# esp8266-blynk.net
KiCad netlist of a schematic drawn in EAGLE
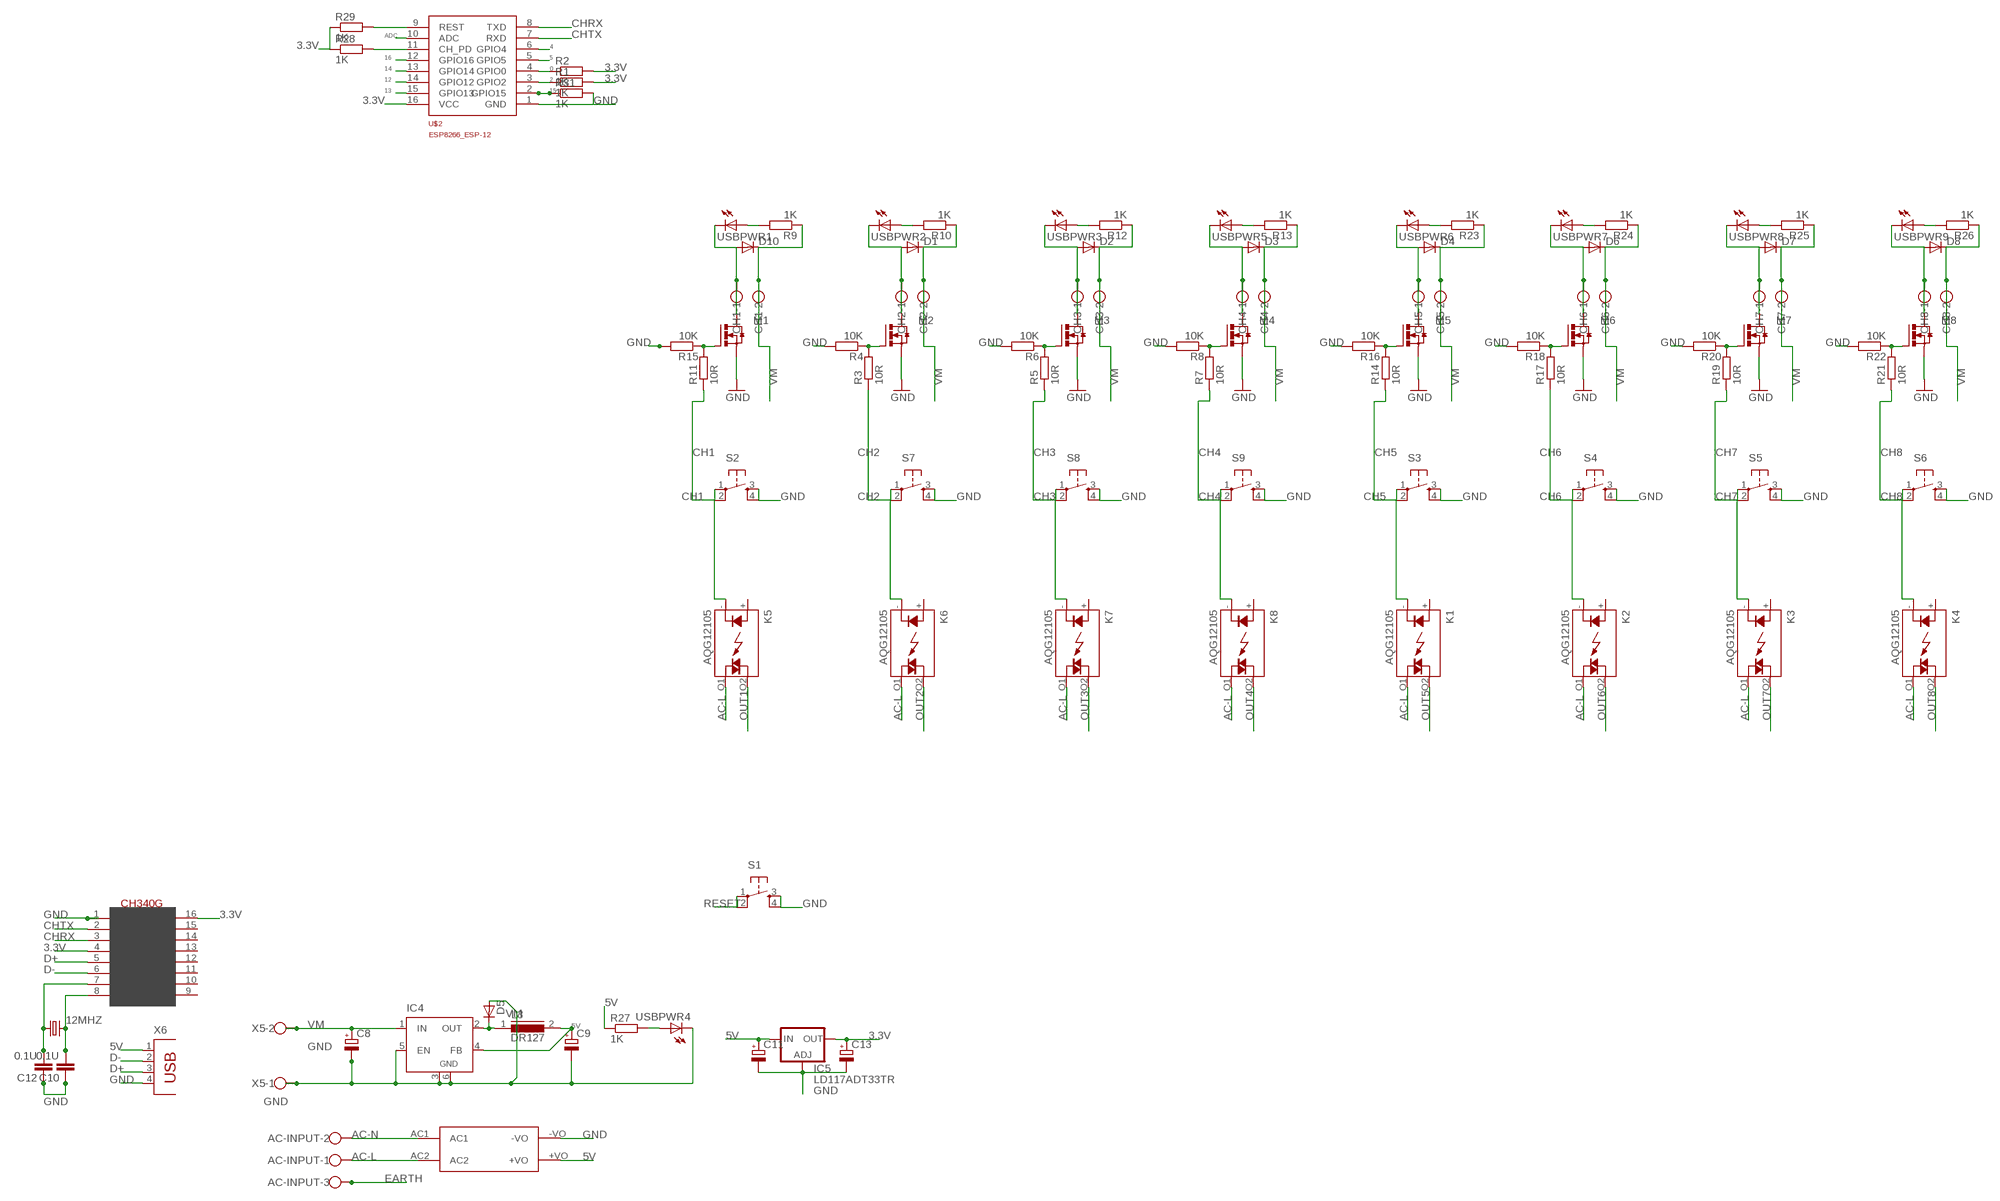
[diagram p0: schematic, sheet 1]

(export (version "E")
  (design (tool "Eeschema 10.0.6"))
  (components
    (comp (ref "12MHZ")
      (value "CRYSTALHC49UP")
      (footprint "eagle-import:HC49UP")
      (libsource (lib "eagle-import") (part "CRYSTALHC49UP"))
    )
    (comp (ref "AC-INPUT")
      (value "W237-103")
      (footprint "eagle-import:W237-103")
      (fields (field (name "MPN") "237-103"))
      (libsource (lib "eagle-import") (part "W237-103"))
    )
    (comp (ref "C8")
      (value "CPOL-EUE")
      (footprint "eagle-import:PANASONIC_E")
      (libsource (lib "eagle-import") (part "resistor_CPOL-EUE"))
    )
    (comp (ref "C9")
      (value "CPOL-EUE")
      (footprint "eagle-import:PANASONIC_E")
      (libsource (lib "eagle-import") (part "resistor_CPOL-EUE"))
    )
    (comp (ref "C10")
      (value "0.1U")
      (footprint "eagle-import:C1206")
      (libsource (lib "eagle-import") (part "C-EUC1206"))
    )
    (comp (ref "C11")
      (value "CPOL-EUC")
      (footprint "eagle-import:PANASONIC_C")
      (libsource (lib "eagle-import") (part "CPOL-EUC"))
    )
    (comp (ref "C12")
      (value "0.1U")
      (footprint "eagle-import:C1206")
      (libsource (lib "eagle-import") (part "C-EUC1206"))
    )
    (comp (ref "C13")
      (value "CPOL-EUC")
      (footprint "eagle-import:PANASONIC_C")
      (libsource (lib "eagle-import") (part "CPOL-EUC"))
    )
    (comp (ref "CH1")
      (value "W237-102")
      (footprint "eagle-import:W237-102")
      (fields (field (name "MPN") "237-102"))
      (libsource (lib "eagle-import") (part "W237-102"))
    )
    (comp (ref "CH2")
      (value "W237-102")
      (footprint "eagle-import:W237-102")
      (fields (field (name "MPN") "237-102"))
      (libsource (lib "eagle-import") (part "W237-102"))
    )
    (comp (ref "CH3")
      (value "W237-102")
      (footprint "eagle-import:W237-102")
      (fields (field (name "MPN") "237-102"))
      (libsource (lib "eagle-import") (part "W237-102"))
    )
    (comp (ref "CH4")
      (value "W237-102")
      (footprint "eagle-import:W237-102")
      (fields (field (name "MPN") "237-102"))
      (libsource (lib "eagle-import") (part "W237-102"))
    )
    (comp (ref "CH5")
      (value "W237-102")
      (footprint "eagle-import:W237-102")
      (fields (field (name "MPN") "237-102"))
      (libsource (lib "eagle-import") (part "W237-102"))
    )
    (comp (ref "CH6")
      (value "W237-102")
      (footprint "eagle-import:W237-102")
      (fields (field (name "MPN") "237-102"))
      (libsource (lib "eagle-import") (part "W237-102"))
    )
    (comp (ref "CH7")
      (value "W237-102")
      (footprint "eagle-import:W237-102")
      (fields (field (name "MPN") "237-102"))
      (libsource (lib "eagle-import") (part "W237-102"))
    )
    (comp (ref "CH8")
      (value "W237-102")
      (footprint "eagle-import:W237-102")
      (fields (field (name "MPN") "237-102"))
      (libsource (lib "eagle-import") (part "W237-102"))
    )
    (comp (ref "D1")
      (value "DIODESMA-ALT")
      (footprint "eagle-import:SMA-DIODE_ALT")
      (libsource (lib "eagle-import") (part "DIODESMA-ALT"))
    )
    (comp (ref "D2")
      (value "DIODESMA-ALT")
      (footprint "eagle-import:SMA-DIODE_ALT")
      (libsource (lib "eagle-import") (part "DIODESMA-ALT"))
    )
    (comp (ref "D3")
      (value "DIODESMA-ALT")
      (footprint "eagle-import:SMA-DIODE_ALT")
      (libsource (lib "eagle-import") (part "DIODESMA-ALT"))
    )
    (comp (ref "D4")
      (value "DIODESMA-ALT")
      (footprint "eagle-import:SMA-DIODE_ALT")
      (libsource (lib "eagle-import") (part "DIODESMA-ALT"))
    )
    (comp (ref "D5")
      (value "D-SOD-87")
      (footprint "eagle-import:SOD87")
      (libsource (lib "eagle-import") (part "D-SOD-87"))
    )
    (comp (ref "D6")
      (value "DIODESMA-ALT")
      (footprint "eagle-import:SMA-DIODE_ALT")
      (libsource (lib "eagle-import") (part "DIODESMA-ALT"))
    )
    (comp (ref "D7")
      (value "DIODESMA-ALT")
      (footprint "eagle-import:SMA-DIODE_ALT")
      (libsource (lib "eagle-import") (part "DIODESMA-ALT"))
    )
    (comp (ref "D8")
      (value "DIODESMA-ALT")
      (footprint "eagle-import:SMA-DIODE_ALT")
      (libsource (lib "eagle-import") (part "DIODESMA-ALT"))
    )
    (comp (ref "D10")
      (value "DIODESMA-ALT")
      (footprint "eagle-import:SMA-DIODE_ALT")
      (libsource (lib "eagle-import") (part "DIODESMA-ALT"))
    )
    (comp (ref "IC4")
      (value "LM2596S")
      (footprint "eagle-import:TO263-5")
      (libsource (lib "eagle-import") (part "LM2596S"))
    )
    (comp (ref "IC5")
      (value "LD117ADT33TR")
      (footprint "eagle-import:DPACK")
      (libsource (lib "eagle-import") (part "LD117A?DT33TR"))
    )
    (comp (ref "K1")
      (value "AQG12105")
      (footprint "eagle-import:AQG")
      (fields (field (name "MF") "AROMAT/ MATSUSHITA"))
      (libsource (lib "eagle-import") (part "AQG12105"))
    )
    (comp (ref "K2")
      (value "AQG12105")
      (footprint "eagle-import:AQG")
      (fields (field (name "MF") "AROMAT/ MATSUSHITA"))
      (libsource (lib "eagle-import") (part "AQG12105"))
    )
    (comp (ref "K3")
      (value "AQG12105")
      (footprint "eagle-import:AQG")
      (fields (field (name "MF") "AROMAT/ MATSUSHITA"))
      (libsource (lib "eagle-import") (part "AQG12105"))
    )
    (comp (ref "K4")
      (value "AQG12105")
      (footprint "eagle-import:AQG")
      (fields (field (name "MF") "AROMAT/ MATSUSHITA"))
      (libsource (lib "eagle-import") (part "AQG12105"))
    )
    (comp (ref "K5")
      (value "AQG12105")
      (footprint "eagle-import:AQG")
      (fields (field (name "MF") "AROMAT/ MATSUSHITA"))
      (libsource (lib "eagle-import") (part "AQG12105"))
    )
    (comp (ref "K6")
      (value "AQG12105")
      (footprint "eagle-import:AQG")
      (fields (field (name "MF") "AROMAT/ MATSUSHITA"))
      (libsource (lib "eagle-import") (part "AQG12105"))
    )
    (comp (ref "K7")
      (value "AQG12105")
      (footprint "eagle-import:AQG")
      (fields (field (name "MF") "AROMAT/ MATSUSHITA"))
      (libsource (lib "eagle-import") (part "AQG12105"))
    )
    (comp (ref "K8")
      (value "AQG12105")
      (footprint "eagle-import:AQG")
      (fields (field (name "MF") "AROMAT/ MATSUSHITA"))
      (libsource (lib "eagle-import") (part "AQG12105"))
    )
    (comp (ref "L3")
      (value "DR127")
      (footprint "eagle-import:DR127")
      (libsource (lib "eagle-import") (part "DR127"))
    )
    (comp (ref "M1")
      (value "IRLR024N")
      (footprint "eagle-import:TO252")
      (libsource (lib "eagle-import") (part "IRLR024N"))
    )
    (comp (ref "M2")
      (value "IRLR024N")
      (footprint "eagle-import:TO252")
      (libsource (lib "eagle-import") (part "IRLR024N"))
    )
    (comp (ref "M3")
      (value "IRLR024N")
      (footprint "eagle-import:TO252")
      (libsource (lib "eagle-import") (part "IRLR024N"))
    )
    (comp (ref "M4")
      (value "IRLR024N")
      (footprint "eagle-import:TO252")
      (libsource (lib "eagle-import") (part "IRLR024N"))
    )
    (comp (ref "M5")
      (value "IRLR024N")
      (footprint "eagle-import:TO252")
      (libsource (lib "eagle-import") (part "IRLR024N"))
    )
    (comp (ref "M6")
      (value "IRLR024N")
      (footprint "eagle-import:TO252")
      (libsource (lib "eagle-import") (part "IRLR024N"))
    )
    (comp (ref "M7")
      (value "IRLR024N")
      (footprint "eagle-import:TO252")
      (libsource (lib "eagle-import") (part "IRLR024N"))
    )
    (comp (ref "M8")
      (value "IRLR024N")
      (footprint "eagle-import:TO252")
      (libsource (lib "eagle-import") (part "IRLR024N"))
    )
    (comp (ref "R1")
      (value "1K")
      (footprint "eagle-import:M1206")
      (libsource (lib "eagle-import") (part "R-EU_M1206"))
    )
    (comp (ref "R2")
      (value "1K")
      (footprint "eagle-import:M1206")
      (libsource (lib "eagle-import") (part "R-EU_M1206"))
    )
    (comp (ref "R3")
      (value "10R")
      (footprint "eagle-import:M1206")
      (libsource (lib "eagle-import") (part "resistor_R-EU_M1206"))
    )
    (comp (ref "R4")
      (value "10K")
      (footprint "eagle-import:M1206")
      (libsource (lib "eagle-import") (part "resistor_R-EU_M1206"))
    )
    (comp (ref "R5")
      (value "10R")
      (footprint "eagle-import:M1206")
      (libsource (lib "eagle-import") (part "resistor_R-EU_M1206"))
    )
    (comp (ref "R6")
      (value "10K")
      (footprint "eagle-import:M1206")
      (libsource (lib "eagle-import") (part "resistor_R-EU_M1206"))
    )
    (comp (ref "R7")
      (value "10R")
      (footprint "eagle-import:M1206")
      (libsource (lib "eagle-import") (part "resistor_R-EU_M1206"))
    )
    (comp (ref "R8")
      (value "10K")
      (footprint "eagle-import:M1206")
      (libsource (lib "eagle-import") (part "resistor_R-EU_M1206"))
    )
    (comp (ref "R9")
      (value "1K")
      (footprint "eagle-import:M1206")
      (libsource (lib "eagle-import") (part "R-EU_M1206"))
    )
    (comp (ref "R10")
      (value "1K")
      (footprint "eagle-import:M1206")
      (libsource (lib "eagle-import") (part "R-EU_M1206"))
    )
    (comp (ref "R11")
      (value "10R")
      (footprint "eagle-import:M1206")
      (libsource (lib "eagle-import") (part "resistor_R-EU_M1206"))
    )
    (comp (ref "R12")
      (value "1K")
      (footprint "eagle-import:M1206")
      (libsource (lib "eagle-import") (part "R-EU_M1206"))
    )
    (comp (ref "R13")
      (value "1K")
      (footprint "eagle-import:M1206")
      (libsource (lib "eagle-import") (part "R-EU_M1206"))
    )
    (comp (ref "R14")
      (value "10R")
      (footprint "eagle-import:M1206")
      (libsource (lib "eagle-import") (part "resistor_R-EU_M1206"))
    )
    (comp (ref "R15")
      (value "10K")
      (footprint "eagle-import:M1206")
      (libsource (lib "eagle-import") (part "resistor_R-EU_M1206"))
    )
    (comp (ref "R16")
      (value "10K")
      (footprint "eagle-import:M1206")
      (libsource (lib "eagle-import") (part "resistor_R-EU_M1206"))
    )
    (comp (ref "R17")
      (value "10R")
      (footprint "eagle-import:M1206")
      (libsource (lib "eagle-import") (part "resistor_R-EU_M1206"))
    )
    (comp (ref "R18")
      (value "10K")
      (footprint "eagle-import:M1206")
      (libsource (lib "eagle-import") (part "resistor_R-EU_M1206"))
    )
    (comp (ref "R19")
      (value "10R")
      (footprint "eagle-import:M1206")
      (libsource (lib "eagle-import") (part "resistor_R-EU_M1206"))
    )
    (comp (ref "R20")
      (value "10K")
      (footprint "eagle-import:M1206")
      (libsource (lib "eagle-import") (part "resistor_R-EU_M1206"))
    )
    (comp (ref "R21")
      (value "10R")
      (footprint "eagle-import:M1206")
      (libsource (lib "eagle-import") (part "resistor_R-EU_M1206"))
    )
    (comp (ref "R22")
      (value "10K")
      (footprint "eagle-import:M1206")
      (libsource (lib "eagle-import") (part "resistor_R-EU_M1206"))
    )
    (comp (ref "R23")
      (value "1K")
      (footprint "eagle-import:M1206")
      (libsource (lib "eagle-import") (part "R-EU_M1206"))
    )
    (comp (ref "R24")
      (value "1K")
      (footprint "eagle-import:M1206")
      (libsource (lib "eagle-import") (part "R-EU_M1206"))
    )
    (comp (ref "R25")
      (value "1K")
      (footprint "eagle-import:M1206")
      (libsource (lib "eagle-import") (part "R-EU_M1206"))
    )
    (comp (ref "R26")
      (value "1K")
      (footprint "eagle-import:M1206")
      (libsource (lib "eagle-import") (part "R-EU_M1206"))
    )
    (comp (ref "R27")
      (value "1K")
      (footprint "eagle-import:M1206")
      (libsource (lib "eagle-import") (part "R-EU_M1206"))
    )
    (comp (ref "R28")
      (value "1K")
      (footprint "eagle-import:M1206")
      (libsource (lib "eagle-import") (part "R-EU_M1206"))
    )
    (comp (ref "R29")
      (value "1K")
      (footprint "eagle-import:M1206")
      (libsource (lib "eagle-import") (part "R-EU_M1206"))
    )
    (comp (ref "R31")
      (value "1K")
      (footprint "eagle-import:M1206")
      (libsource (lib "eagle-import") (part "R-EU_M1206"))
    )
    (comp (ref "S1")
      (value "TAC_SWITCHPTH")
      (footprint "eagle-import:TACTILE-PTH")
      (libsource (lib "eagle-import") (part "TAC_SWITCHPTH"))
    )
    (comp (ref "S2")
      (value "TAC_SWITCHPTH")
      (footprint "eagle-import:TACTILE-PTH")
      (libsource (lib "eagle-import") (part "TAC_SWITCHPTH"))
    )
    (comp (ref "S3")
      (value "TAC_SWITCHPTH")
      (footprint "eagle-import:TACTILE-PTH")
      (libsource (lib "eagle-import") (part "TAC_SWITCHPTH"))
    )
    (comp (ref "S4")
      (value "TAC_SWITCHPTH")
      (footprint "eagle-import:TACTILE-PTH")
      (libsource (lib "eagle-import") (part "TAC_SWITCHPTH"))
    )
    (comp (ref "S5")
      (value "TAC_SWITCHPTH")
      (footprint "eagle-import:TACTILE-PTH")
      (libsource (lib "eagle-import") (part "TAC_SWITCHPTH"))
    )
    (comp (ref "S6")
      (value "TAC_SWITCHPTH")
      (footprint "eagle-import:TACTILE-PTH")
      (libsource (lib "eagle-import") (part "TAC_SWITCHPTH"))
    )
    (comp (ref "S7")
      (value "TAC_SWITCHPTH")
      (footprint "eagle-import:TACTILE-PTH")
      (libsource (lib "eagle-import") (part "TAC_SWITCHPTH"))
    )
    (comp (ref "S8")
      (value "TAC_SWITCHPTH")
      (footprint "eagle-import:TACTILE-PTH")
      (libsource (lib "eagle-import") (part "TAC_SWITCHPTH"))
    )
    (comp (ref "S9")
      (value "TAC_SWITCHPTH")
      (footprint "eagle-import:TACTILE-PTH")
      (libsource (lib "eagle-import") (part "TAC_SWITCHPTH"))
    )
    (comp (ref "U$1")
      (value "HLK-PM01")
      (footprint "eagle-import:HLK-PM01")
      (libsource (lib "eagle-import") (part "HLK-PM01"))
    )
    (comp (ref "U$2")
      (value "ESP8266_ESP-12")
      (footprint "eagle-import:ESP8266-ESP12")
      (libsource (lib "eagle-import") (part "ESP8266_ESP-12"))
    )
    (comp (ref "U$4")
      (value "CH340G")
      (footprint "eagle-import:SOIC16")
      (libsource (lib "eagle-import") (part "CH340G"))
    )
    (comp (ref "USBPWR1")
      (value "LED3MM")
      (footprint "eagle-import:LED3MM")
      (libsource (lib "eagle-import") (part "LED3MM"))
    )
    (comp (ref "USBPWR2")
      (value "LED3MM")
      (footprint "eagle-import:LED3MM")
      (libsource (lib "eagle-import") (part "LED3MM"))
    )
    (comp (ref "USBPWR3")
      (value "LED3MM")
      (footprint "eagle-import:LED3MM")
      (libsource (lib "eagle-import") (part "LED3MM"))
    )
    (comp (ref "USBPWR4")
      (value "LED3MM")
      (footprint "eagle-import:LED3MM")
      (libsource (lib "eagle-import") (part "LED3MM"))
    )
    (comp (ref "USBPWR5")
      (value "LED3MM")
      (footprint "eagle-import:LED3MM")
      (libsource (lib "eagle-import") (part "LED3MM"))
    )
    (comp (ref "USBPWR6")
      (value "LED3MM")
      (footprint "eagle-import:LED3MM")
      (libsource (lib "eagle-import") (part "LED3MM"))
    )
    (comp (ref "USBPWR7")
      (value "LED3MM")
      (footprint "eagle-import:LED3MM")
      (libsource (lib "eagle-import") (part "LED3MM"))
    )
    (comp (ref "USBPWR8")
      (value "LED3MM")
      (footprint "eagle-import:LED3MM")
      (libsource (lib "eagle-import") (part "LED3MM"))
    )
    (comp (ref "USBPWR9")
      (value "LED3MM")
      (footprint "eagle-import:LED3MM")
      (libsource (lib "eagle-import") (part "LED3MM"))
    )
    (comp (ref "X5")
      (value "W237-102")
      (footprint "eagle-import:W237-102")
      (fields (field (name "MPN") "237-102"))
      (libsource (lib "eagle-import") (part "W237-102"))
    )
    (comp (ref "X6")
      (value "PN61729")
      (footprint "eagle-import:PN61729")
      (libsource (lib "eagle-import") (part "PN61729"))
    )
  )
  (nets
    (net (code "1") (name "/0") (class "Default")
      (node (ref "R2") (pin "1") (pinfunction "1_1") (pintype "passive"))
      (node (ref "U$2") (pin "4") (pinfunction "GPIO0_4") (pintype "bidirectional"))
    )
    (net (code "2") (name "/2") (class "Default")
      (node (ref "R1") (pin "1") (pinfunction "1_1") (pintype "passive"))
      (node (ref "U$2") (pin "3") (pinfunction "GPIO2_3") (pintype "bidirectional"))
    )
    (net (code "3") (name "/3.3V") (class "Default")
      (node (ref "C13") (pin "+") (pinfunction "+_+") (pintype "passive"))
      (node (ref "IC5") (pin "4") (pinfunction "OUT_4") (pintype "passive"))
      (node (ref "R1") (pin "2") (pinfunction "2_2") (pintype "passive"))
      (node (ref "R2") (pin "2") (pinfunction "2_2") (pintype "passive"))
      (node (ref "R28") (pin "1") (pinfunction "1_1") (pintype "passive"))
      (node (ref "R29") (pin "1") (pinfunction "1_1") (pintype "passive"))
      (node (ref "U$2") (pin "16") (pinfunction "VCC_16") (pintype "bidirectional"))
      (node (ref "U$4") (pin "16") (pinfunction "VCC_16") (pintype "bidirectional"))
      (node (ref "U$4") (pin "4") (pinfunction "V3_4") (pintype "bidirectional"))
    )
    (net (code "4") (name "/4") (class "Default")
      (node (ref "U$2") (pin "6") (pinfunction "GPIO4_6") (pintype "bidirectional"))
    )
    (net (code "5") (name "/5") (class "Default")
      (node (ref "U$2") (pin "5") (pinfunction "GPIO5_5") (pintype "bidirectional"))
    )
    (net (code "6") (name "/5V") (class "Default")
      (node (ref "C11") (pin "+") (pinfunction "+_+") (pintype "passive"))
      (node (ref "C9") (pin "+") (pinfunction "+_+") (pintype "passive"))
      (node (ref "IC4") (pin "4") (pinfunction "FB_4") (pintype "input"))
      (node (ref "IC5") (pin "3") (pinfunction "IN_3") (pintype "input"))
      (node (ref "L3") (pin "2") (pinfunction "2_2") (pintype "passive"))
      (node (ref "R27") (pin "1") (pinfunction "1_1") (pintype "passive"))
      (node (ref "U$1") (pin "+VO") (pinfunction "+VO_+VO") (pintype "bidirectional"))
      (node (ref "X6") (pin "1") (pinfunction "1_1") (pintype "passive"))
    )
    (net (code "7") (name "/12") (class "Default")
      (node (ref "U$2") (pin "14") (pinfunction "GPIO12_14") (pintype "bidirectional"))
    )
    (net (code "8") (name "/13") (class "Default")
      (node (ref "U$2") (pin "15") (pinfunction "GPIO13_15") (pintype "bidirectional"))
    )
    (net (code "9") (name "/14") (class "Default")
      (node (ref "U$2") (pin "13") (pinfunction "GPIO14_13") (pintype "bidirectional"))
    )
    (net (code "10") (name "/15") (class "Default")
      (node (ref "R31") (pin "1") (pinfunction "1_1") (pintype "passive"))
      (node (ref "U$2") (pin "2") (pinfunction "GPIO15_2") (pintype "bidirectional"))
    )
    (net (code "11") (name "/16") (class "Default")
      (node (ref "U$2") (pin "12") (pinfunction "GPIO16_12") (pintype "bidirectional"))
    )
    (net (code "12") (name "/AC-L") (class "Default")
      (node (ref "AC-INPUT") (pin "1") (pinfunction "KL_1") (pintype "passive"))
      (node (ref "K1") (pin "O1") (pinfunction "DS2_O1") (pintype "passive"))
      (node (ref "K2") (pin "O1") (pinfunction "DS2_O1") (pintype "passive"))
      (node (ref "K3") (pin "O1") (pinfunction "DS2_O1") (pintype "passive"))
      (node (ref "K4") (pin "O1") (pinfunction "DS2_O1") (pintype "passive"))
      (node (ref "K5") (pin "O1") (pinfunction "DS2_O1") (pintype "passive"))
      (node (ref "K6") (pin "O1") (pinfunction "DS2_O1") (pintype "passive"))
      (node (ref "K7") (pin "O1") (pinfunction "DS2_O1") (pintype "passive"))
      (node (ref "K8") (pin "O1") (pinfunction "DS2_O1") (pintype "passive"))
      (node (ref "U$1") (pin "AC2") (pinfunction "AC2_AC2") (pintype "bidirectional"))
    )
    (net (code "13") (name "/AC-N") (class "Default")
      (node (ref "AC-INPUT") (pin "2") (pinfunction "KL_2") (pintype "passive"))
      (node (ref "U$1") (pin "AC1") (pinfunction "AC1_AC1") (pintype "bidirectional"))
    )
    (net (code "14") (name "/ADC") (class "Default")
      (node (ref "U$2") (pin "10") (pinfunction "ADC_10") (pintype "bidirectional"))
    )
    (net (code "15") (name "/CH1") (class "Default")
      (node (ref "K5") (pin "-") (pinfunction "K_-") (pintype "passive"))
      (node (ref "R11") (pin "1") (pinfunction "1_1") (pintype "passive"))
      (node (ref "S2") (pin "1") (pinfunction "1_1") (pintype "passive"))
      (node (ref "S2") (pin "2") (pinfunction "2_2") (pintype "passive"))
    )
    (net (code "16") (name "/CH2") (class "Default")
      (node (ref "K6") (pin "-") (pinfunction "K_-") (pintype "passive"))
      (node (ref "R3") (pin "1") (pinfunction "1_1") (pintype "passive"))
      (node (ref "S7") (pin "1") (pinfunction "1_1") (pintype "passive"))
      (node (ref "S7") (pin "2") (pinfunction "2_2") (pintype "passive"))
    )
    (net (code "17") (name "/CH3") (class "Default")
      (node (ref "K7") (pin "-") (pinfunction "K_-") (pintype "passive"))
      (node (ref "R5") (pin "1") (pinfunction "1_1") (pintype "passive"))
      (node (ref "S8") (pin "1") (pinfunction "1_1") (pintype "passive"))
      (node (ref "S8") (pin "2") (pinfunction "2_2") (pintype "passive"))
    )
    (net (code "18") (name "/CH4") (class "Default")
      (node (ref "K8") (pin "-") (pinfunction "K_-") (pintype "passive"))
      (node (ref "R7") (pin "1") (pinfunction "1_1") (pintype "passive"))
      (node (ref "S9") (pin "1") (pinfunction "1_1") (pintype "passive"))
      (node (ref "S9") (pin "2") (pinfunction "2_2") (pintype "passive"))
    )
    (net (code "19") (name "/CH5") (class "Default")
      (node (ref "K1") (pin "-") (pinfunction "K_-") (pintype "passive"))
      (node (ref "R14") (pin "1") (pinfunction "1_1") (pintype "passive"))
      (node (ref "S3") (pin "1") (pinfunction "1_1") (pintype "passive"))
      (node (ref "S3") (pin "2") (pinfunction "2_2") (pintype "passive"))
    )
    (net (code "20") (name "/CH6") (class "Default")
      (node (ref "K2") (pin "-") (pinfunction "K_-") (pintype "passive"))
      (node (ref "R17") (pin "1") (pinfunction "1_1") (pintype "passive"))
      (node (ref "S4") (pin "1") (pinfunction "1_1") (pintype "passive"))
      (node (ref "S4") (pin "2") (pinfunction "2_2") (pintype "passive"))
    )
    (net (code "21") (name "/CH7") (class "Default")
      (node (ref "K3") (pin "-") (pinfunction "K_-") (pintype "passive"))
      (node (ref "R19") (pin "1") (pinfunction "1_1") (pintype "passive"))
      (node (ref "S5") (pin "1") (pinfunction "1_1") (pintype "passive"))
      (node (ref "S5") (pin "2") (pinfunction "2_2") (pintype "passive"))
    )
    (net (code "22") (name "/CH8") (class "Default")
      (node (ref "K4") (pin "-") (pinfunction "K_-") (pintype "passive"))
      (node (ref "R21") (pin "1") (pinfunction "1_1") (pintype "passive"))
      (node (ref "S6") (pin "1") (pinfunction "1_1") (pintype "passive"))
      (node (ref "S6") (pin "2") (pinfunction "2_2") (pintype "passive"))
    )
    (net (code "23") (name "/CHRX") (class "Default")
      (node (ref "U$2") (pin "8") (pinfunction "TXD_8") (pintype "bidirectional"))
      (node (ref "U$4") (pin "3") (pinfunction "RX_3") (pintype "bidirectional"))
    )
    (net (code "24") (name "/CHTX") (class "Default")
      (node (ref "U$2") (pin "7") (pinfunction "RXD_7") (pintype "bidirectional"))
      (node (ref "U$4") (pin "2") (pinfunction "TX_2") (pintype "bidirectional"))
    )
    (net (code "25") (name "/D+") (class "Default")
      (node (ref "U$4") (pin "5") (pinfunction "D+_5") (pintype "bidirectional"))
      (node (ref "X6") (pin "3") (pinfunction "3_3") (pintype "passive"))
    )
    (net (code "26") (name "/D-") (class "Default")
      (node (ref "U$4") (pin "6") (pinfunction "D-_6") (pintype "bidirectional"))
      (node (ref "X6") (pin "2") (pinfunction "2_2") (pintype "passive"))
    )
    (net (code "27") (name "/EARTH") (class "Default")
      (node (ref "AC-INPUT") (pin "3") (pinfunction "KL_3") (pintype "passive"))
    )
    (net (code "28") (name "/OUT1") (class "Default")
      (node (ref "CH1") (pin "1") (pinfunction "KL_1") (pintype "passive"))
      (node (ref "D10") (pin "A") (pinfunction "A_A") (pintype "passive"))
      (node (ref "K5") (pin "O2") (pinfunction "DS1_O2") (pintype "passive"))
      (node (ref "M1") (pin "3") (pinfunction "D_3") (pintype "passive"))
      (node (ref "USBPWR1") (pin "K") (pinfunction "C_K") (pintype "passive"))
    )
    (net (code "29") (name "/OUT2") (class "Default")
      (node (ref "CH2") (pin "1") (pinfunction "KL_1") (pintype "passive"))
      (node (ref "D1") (pin "A") (pinfunction "A_A") (pintype "passive"))
      (node (ref "K6") (pin "O2") (pinfunction "DS1_O2") (pintype "passive"))
      (node (ref "M2") (pin "3") (pinfunction "D_3") (pintype "passive"))
      (node (ref "USBPWR2") (pin "K") (pinfunction "C_K") (pintype "passive"))
    )
    (net (code "30") (name "/OUT3") (class "Default")
      (node (ref "CH3") (pin "1") (pinfunction "KL_1") (pintype "passive"))
      (node (ref "D2") (pin "A") (pinfunction "A_A") (pintype "passive"))
      (node (ref "K7") (pin "O2") (pinfunction "DS1_O2") (pintype "passive"))
      (node (ref "M3") (pin "3") (pinfunction "D_3") (pintype "passive"))
      (node (ref "USBPWR3") (pin "K") (pinfunction "C_K") (pintype "passive"))
    )
    (net (code "31") (name "/OUT4") (class "Default")
      (node (ref "CH4") (pin "1") (pinfunction "KL_1") (pintype "passive"))
      (node (ref "D3") (pin "A") (pinfunction "A_A") (pintype "passive"))
      (node (ref "K8") (pin "O2") (pinfunction "DS1_O2") (pintype "passive"))
      (node (ref "M4") (pin "3") (pinfunction "D_3") (pintype "passive"))
      (node (ref "USBPWR5") (pin "K") (pinfunction "C_K") (pintype "passive"))
    )
    (net (code "32") (name "/OUT5") (class "Default")
      (node (ref "CH5") (pin "1") (pinfunction "KL_1") (pintype "passive"))
      (node (ref "D4") (pin "A") (pinfunction "A_A") (pintype "passive"))
      (node (ref "K1") (pin "O2") (pinfunction "DS1_O2") (pintype "passive"))
      (node (ref "M5") (pin "3") (pinfunction "D_3") (pintype "passive"))
      (node (ref "USBPWR6") (pin "K") (pinfunction "C_K") (pintype "passive"))
    )
    (net (code "33") (name "/OUT6") (class "Default")
      (node (ref "CH6") (pin "1") (pinfunction "KL_1") (pintype "passive"))
      (node (ref "D6") (pin "A") (pinfunction "A_A") (pintype "passive"))
      (node (ref "K2") (pin "O2") (pinfunction "DS1_O2") (pintype "passive"))
      (node (ref "M6") (pin "3") (pinfunction "D_3") (pintype "passive"))
      (node (ref "USBPWR7") (pin "K") (pinfunction "C_K") (pintype "passive"))
    )
    (net (code "34") (name "/OUT7") (class "Default")
      (node (ref "CH7") (pin "1") (pinfunction "KL_1") (pintype "passive"))
      (node (ref "D7") (pin "A") (pinfunction "A_A") (pintype "passive"))
      (node (ref "K3") (pin "O2") (pinfunction "DS1_O2") (pintype "passive"))
      (node (ref "M7") (pin "3") (pinfunction "D_3") (pintype "passive"))
      (node (ref "USBPWR8") (pin "K") (pinfunction "C_K") (pintype "passive"))
    )
    (net (code "35") (name "/OUT8") (class "Default")
      (node (ref "CH8") (pin "1") (pinfunction "KL_1") (pintype "passive"))
      (node (ref "D8") (pin "A") (pinfunction "A_A") (pintype "passive"))
      (node (ref "K4") (pin "O2") (pinfunction "DS1_O2") (pintype "passive"))
      (node (ref "M8") (pin "3") (pinfunction "D_3") (pintype "passive"))
      (node (ref "USBPWR9") (pin "K") (pinfunction "C_K") (pintype "passive"))
    )
    (net (code "36") (name "/RESET") (class "Default")
      (node (ref "R29") (pin "2") (pinfunction "2_2") (pintype "passive"))
      (node (ref "S1") (pin "1") (pinfunction "1_1") (pintype "passive"))
      (node (ref "S1") (pin "2") (pinfunction "2_2") (pintype "passive"))
      (node (ref "U$2") (pin "9") (pinfunction "REST_9") (pintype "bidirectional"))
    )
    (net (code "37") (name "/VM") (class "Default")
      (node (ref "C8") (pin "+") (pinfunction "+_+") (pintype "passive"))
      (node (ref "CH1") (pin "2") (pinfunction "KL_2") (pintype "passive"))
      (node (ref "CH2") (pin "2") (pinfunction "KL_2") (pintype "passive"))
      (node (ref "CH3") (pin "2") (pinfunction "KL_2") (pintype "passive"))
      (node (ref "CH4") (pin "2") (pinfunction "KL_2") (pintype "passive"))
      (node (ref "CH5") (pin "2") (pinfunction "KL_2") (pintype "passive"))
      (node (ref "CH6") (pin "2") (pinfunction "KL_2") (pintype "passive"))
      (node (ref "CH7") (pin "2") (pinfunction "KL_2") (pintype "passive"))
      (node (ref "CH8") (pin "2") (pinfunction "KL_2") (pintype "passive"))
      (node (ref "D1") (pin "C") (pinfunction "C_C") (pintype "passive"))
      (node (ref "D10") (pin "C") (pinfunction "C_C") (pintype "passive"))
      (node (ref "D2") (pin "C") (pinfunction "C_C") (pintype "passive"))
      (node (ref "D3") (pin "C") (pinfunction "C_C") (pintype "passive"))
      (node (ref "D4") (pin "C") (pinfunction "C_C") (pintype "passive"))
      (node (ref "D6") (pin "C") (pinfunction "C_C") (pintype "passive"))
      (node (ref "D7") (pin "C") (pinfunction "C_C") (pintype "passive"))
      (node (ref "D8") (pin "C") (pinfunction "C_C") (pintype "passive"))
      (node (ref "IC4") (pin "1") (pinfunction "IN_1") (pintype "input"))
      (node (ref "R10") (pin "1") (pinfunction "1_1") (pintype "passive"))
      (node (ref "R12") (pin "1") (pinfunction "1_1") (pintype "passive"))
      (node (ref "R13") (pin "1") (pinfunction "1_1") (pintype "passive"))
      (node (ref "R23") (pin "1") (pinfunction "1_1") (pintype "passive"))
      (node (ref "R24") (pin "1") (pinfunction "1_1") (pintype "passive"))
      (node (ref "R25") (pin "1") (pinfunction "1_1") (pintype "passive"))
      (node (ref "R26") (pin "1") (pinfunction "1_1") (pintype "passive"))
      (node (ref "R9") (pin "1") (pinfunction "1_1") (pintype "passive"))
      (node (ref "X5") (pin "2") (pinfunction "KL_2") (pintype "passive"))
    )
    (net (code "38") (name "GND") (class "Default")
      (node (ref "C10") (pin "1") (pinfunction "1_1") (pintype "passive"))
      (node (ref "C11") (pin "-") (pinfunction "-_-") (pintype "passive"))
      (node (ref "C12") (pin "1") (pinfunction "1_1") (pintype "passive"))
      (node (ref "C13") (pin "-") (pinfunction "-_-") (pintype "passive"))
      (node (ref "C8") (pin "-") (pinfunction "-_-") (pintype "passive"))
      (node (ref "C9") (pin "-") (pinfunction "-_-") (pintype "passive"))
      (node (ref "D5") (pin "2") (pinfunction "A_2") (pintype "passive"))
      (node (ref "IC4") (pin "3") (pinfunction "GND_3") (pintype "power_in"))
      (node (ref "IC4") (pin "5") (pinfunction "EN_5") (pintype "input"))
      (node (ref "IC4") (pin "6") (pinfunction "GND_6") (pintype "power_in"))
      (node (ref "IC5") (pin "1") (pinfunction "ADJ_1") (pintype "input"))
      (node (ref "M1") (pin "2") (pinfunction "S_2") (pintype "passive"))
      (node (ref "M2") (pin "2") (pinfunction "S_2") (pintype "passive"))
      (node (ref "M3") (pin "2") (pinfunction "S_2") (pintype "passive"))
      (node (ref "M4") (pin "2") (pinfunction "S_2") (pintype "passive"))
      (node (ref "M5") (pin "2") (pinfunction "S_2") (pintype "passive"))
      (node (ref "M6") (pin "2") (pinfunction "S_2") (pintype "passive"))
      (node (ref "M7") (pin "2") (pinfunction "S_2") (pintype "passive"))
      (node (ref "M8") (pin "2") (pinfunction "S_2") (pintype "passive"))
      (node (ref "R15") (pin "2") (pinfunction "2_2") (pintype "passive"))
      (node (ref "R16") (pin "2") (pinfunction "2_2") (pintype "passive"))
      (node (ref "R18") (pin "2") (pinfunction "2_2") (pintype "passive"))
      (node (ref "R20") (pin "2") (pinfunction "2_2") (pintype "passive"))
      (node (ref "R22") (pin "2") (pinfunction "2_2") (pintype "passive"))
      (node (ref "R31") (pin "2") (pinfunction "2_2") (pintype "passive"))
      (node (ref "R4") (pin "2") (pinfunction "2_2") (pintype "passive"))
      (node (ref "R6") (pin "2") (pinfunction "2_2") (pintype "passive"))
      (node (ref "R8") (pin "2") (pinfunction "2_2") (pintype "passive"))
      (node (ref "S1") (pin "3") (pinfunction "3_3") (pintype "passive"))
      (node (ref "S1") (pin "4") (pinfunction "4_4") (pintype "passive"))
      (node (ref "S2") (pin "3") (pinfunction "3_3") (pintype "passive"))
      (node (ref "S2") (pin "4") (pinfunction "4_4") (pintype "passive"))
      (node (ref "S3") (pin "3") (pinfunction "3_3") (pintype "passive"))
      (node (ref "S3") (pin "4") (pinfunction "4_4") (pintype "passive"))
      (node (ref "S4") (pin "3") (pinfunction "3_3") (pintype "passive"))
      (node (ref "S4") (pin "4") (pinfunction "4_4") (pintype "passive"))
      (node (ref "S5") (pin "3") (pinfunction "3_3") (pintype "passive"))
      (node (ref "S5") (pin "4") (pinfunction "4_4") (pintype "passive"))
      (node (ref "S6") (pin "3") (pinfunction "3_3") (pintype "passive"))
      (node (ref "S6") (pin "4") (pinfunction "4_4") (pintype "passive"))
      (node (ref "S7") (pin "3") (pinfunction "3_3") (pintype "passive"))
      (node (ref "S7") (pin "4") (pinfunction "4_4") (pintype "passive"))
      (node (ref "S8") (pin "3") (pinfunction "3_3") (pintype "passive"))
      (node (ref "S8") (pin "4") (pinfunction "4_4") (pintype "passive"))
      (node (ref "S9") (pin "3") (pinfunction "3_3") (pintype "passive"))
      (node (ref "S9") (pin "4") (pinfunction "4_4") (pintype "passive"))
      (node (ref "U$1") (pin "-VO") (pinfunction "-VO_-VO") (pintype "bidirectional"))
      (node (ref "U$2") (pin "1") (pinfunction "GND_1") (pintype "bidirectional"))
      (node (ref "U$4") (pin "1") (pinfunction "GND_1") (pintype "bidirectional"))
      (node (ref "USBPWR4") (pin "K") (pinfunction "C_K") (pintype "passive"))
      (node (ref "X5") (pin "1") (pinfunction "KL_1") (pintype "passive"))
      (node (ref "X6") (pin "4") (pinfunction "4_4") (pintype "passive"))
    )
    (net (code "39") (name "Net-(D5-C)") (class "Default")
      (node (ref "D5") (pin "1") (pinfunction "C_1") (pintype "passive"))
      (node (ref "IC4") (pin "2") (pinfunction "OUT_2") (pintype "output"))
      (node (ref "L3") (pin "1") (pinfunction "1_1") (pintype "passive"))
    )
    (net (code "40") (name "Net-(M1-G)") (class "Default")
      (node (ref "M1") (pin "1") (pinfunction "G_1") (pintype "passive"))
      (node (ref "R11") (pin "2") (pinfunction "2_2") (pintype "passive"))
      (node (ref "R15") (pin "1") (pinfunction "1_1") (pintype "passive"))
    )
    (net (code "41") (name "Net-(M2-G)") (class "Default")
      (node (ref "M2") (pin "1") (pinfunction "G_1") (pintype "passive"))
      (node (ref "R3") (pin "2") (pinfunction "2_2") (pintype "passive"))
      (node (ref "R4") (pin "1") (pinfunction "1_1") (pintype "passive"))
    )
    (net (code "42") (name "Net-(M3-G)") (class "Default")
      (node (ref "M3") (pin "1") (pinfunction "G_1") (pintype "passive"))
      (node (ref "R5") (pin "2") (pinfunction "2_2") (pintype "passive"))
      (node (ref "R6") (pin "1") (pinfunction "1_1") (pintype "passive"))
    )
    (net (code "43") (name "Net-(M4-G)") (class "Default")
      (node (ref "M4") (pin "1") (pinfunction "G_1") (pintype "passive"))
      (node (ref "R7") (pin "2") (pinfunction "2_2") (pintype "passive"))
      (node (ref "R8") (pin "1") (pinfunction "1_1") (pintype "passive"))
    )
    (net (code "44") (name "Net-(M5-G)") (class "Default")
      (node (ref "M5") (pin "1") (pinfunction "G_1") (pintype "passive"))
      (node (ref "R14") (pin "2") (pinfunction "2_2") (pintype "passive"))
      (node (ref "R16") (pin "1") (pinfunction "1_1") (pintype "passive"))
    )
    (net (code "45") (name "Net-(M6-G)") (class "Default")
      (node (ref "M6") (pin "1") (pinfunction "G_1") (pintype "passive"))
      (node (ref "R17") (pin "2") (pinfunction "2_2") (pintype "passive"))
      (node (ref "R18") (pin "1") (pinfunction "1_1") (pintype "passive"))
    )
    (net (code "46") (name "Net-(M7-G)") (class "Default")
      (node (ref "M7") (pin "1") (pinfunction "G_1") (pintype "passive"))
      (node (ref "R19") (pin "2") (pinfunction "2_2") (pintype "passive"))
      (node (ref "R20") (pin "1") (pinfunction "1_1") (pintype "passive"))
    )
    (net (code "47") (name "Net-(M8-G)") (class "Default")
      (node (ref "M8") (pin "1") (pinfunction "G_1") (pintype "passive"))
      (node (ref "R21") (pin "2") (pinfunction "2_2") (pintype "passive"))
      (node (ref "R22") (pin "1") (pinfunction "1_1") (pintype "passive"))
    )
    (net (code "48") (name "Net-(R9-Pad2)") (class "Default")
      (node (ref "R9") (pin "2") (pinfunction "2_2") (pintype "passive"))
      (node (ref "USBPWR1") (pin "A") (pinfunction "A_A") (pintype "passive"))
    )
    (net (code "49") (name "Net-(R10-Pad2)") (class "Default")
      (node (ref "R10") (pin "2") (pinfunction "2_2") (pintype "passive"))
      (node (ref "USBPWR2") (pin "A") (pinfunction "A_A") (pintype "passive"))
    )
    (net (code "50") (name "Net-(R12-Pad2)") (class "Default")
      (node (ref "R12") (pin "2") (pinfunction "2_2") (pintype "passive"))
      (node (ref "USBPWR3") (pin "A") (pinfunction "A_A") (pintype "passive"))
    )
    (net (code "51") (name "Net-(R13-Pad2)") (class "Default")
      (node (ref "R13") (pin "2") (pinfunction "2_2") (pintype "passive"))
      (node (ref "USBPWR5") (pin "A") (pinfunction "A_A") (pintype "passive"))
    )
    (net (code "52") (name "Net-(R23-Pad2)") (class "Default")
      (node (ref "R23") (pin "2") (pinfunction "2_2") (pintype "passive"))
      (node (ref "USBPWR6") (pin "A") (pinfunction "A_A") (pintype "passive"))
    )
    (net (code "53") (name "Net-(R24-Pad2)") (class "Default")
      (node (ref "R24") (pin "2") (pinfunction "2_2") (pintype "passive"))
      (node (ref "USBPWR7") (pin "A") (pinfunction "A_A") (pintype "passive"))
    )
    (net (code "54") (name "Net-(R25-Pad2)") (class "Default")
      (node (ref "R25") (pin "2") (pinfunction "2_2") (pintype "passive"))
      (node (ref "USBPWR8") (pin "A") (pinfunction "A_A") (pintype "passive"))
    )
    (net (code "55") (name "Net-(R26-Pad2)") (class "Default")
      (node (ref "R26") (pin "2") (pinfunction "2_2") (pintype "passive"))
      (node (ref "USBPWR9") (pin "A") (pinfunction "A_A") (pintype "passive"))
    )
    (net (code "56") (name "Net-(R27-Pad2)") (class "Default")
      (node (ref "R27") (pin "2") (pinfunction "2_2") (pintype "passive"))
      (node (ref "USBPWR4") (pin "A") (pinfunction "A_A") (pintype "passive"))
    )
    (net (code "57") (name "Net-(U$2-CH_PD)") (class "Default")
      (node (ref "R28") (pin "2") (pinfunction "2_2") (pintype "passive"))
      (node (ref "U$2") (pin "11") (pinfunction "CH_PD_11") (pintype "bidirectional"))
    )
    (net (code "58") (name "Net-(U$4-XI)") (class "Default")
      (node (ref "12MHZ") (pin "1") (pinfunction "1_1") (pintype "passive"))
      (node (ref "C12") (pin "2") (pinfunction "2_2") (pintype "passive"))
      (node (ref "U$4") (pin "7") (pinfunction "XI_7") (pintype "bidirectional"))
    )
    (net (code "59") (name "Net-(U$4-XO)") (class "Default")
      (node (ref "12MHZ") (pin "2") (pinfunction "2_2") (pintype "passive"))
      (node (ref "C10") (pin "2") (pinfunction "2_2") (pintype "passive"))
      (node (ref "U$4") (pin "8") (pinfunction "XO_8") (pintype "bidirectional"))
    )
    (net (code "60") (name "unconnected-(K1-A-Pad+)") (class "Default")
      (node (ref "K1") (pin "+") (pinfunction "A_+") (pintype "passive"))
    )
    (net (code "61") (name "unconnected-(K2-A-Pad+)") (class "Default")
      (node (ref "K2") (pin "+") (pinfunction "A_+") (pintype "passive"))
    )
    (net (code "62") (name "unconnected-(K3-A-Pad+)") (class "Default")
      (node (ref "K3") (pin "+") (pinfunction "A_+") (pintype "passive"))
    )
    (net (code "63") (name "unconnected-(K4-A-Pad+)") (class "Default")
      (node (ref "K4") (pin "+") (pinfunction "A_+") (pintype "passive"))
    )
    (net (code "64") (name "unconnected-(K5-A-Pad+)") (class "Default")
      (node (ref "K5") (pin "+") (pinfunction "A_+") (pintype "passive"))
    )
    (net (code "65") (name "unconnected-(K6-A-Pad+)") (class "Default")
      (node (ref "K6") (pin "+") (pinfunction "A_+") (pintype "passive"))
    )
    (net (code "66") (name "unconnected-(K7-A-Pad+)") (class "Default")
      (node (ref "K7") (pin "+") (pinfunction "A_+") (pintype "passive"))
    )
    (net (code "67") (name "unconnected-(K8-A-Pad+)") (class "Default")
      (node (ref "K8") (pin "+") (pinfunction "A_+") (pintype "passive"))
    )
    (net (code "68") (name "unconnected-(U$4-CTS-Pad9)") (class "Default")
      (node (ref "U$4") (pin "9") (pinfunction "CTS_9") (pintype "bidirectional"))
    )
    (net (code "69") (name "unconnected-(U$4-DCD-Pad12)") (class "Default")
      (node (ref "U$4") (pin "12") (pinfunction "DCD_12") (pintype "bidirectional"))
    )
    (net (code "70") (name "unconnected-(U$4-DSR-Pad10)") (class "Default")
      (node (ref "U$4") (pin "10") (pinfunction "DSR_10") (pintype "bidirectional"))
    )
    (net (code "71") (name "unconnected-(U$4-DTR-Pad13)") (class "Default")
      (node (ref "U$4") (pin "13") (pinfunction "DTR_13") (pintype "bidirectional"))
    )
    (net (code "72") (name "unconnected-(U$4-RI-Pad11)") (class "Default")
      (node (ref "U$4") (pin "11") (pinfunction "RI_11") (pintype "bidirectional"))
    )
    (net (code "73") (name "unconnected-(U$4-RS232-Pad15)") (class "Default")
      (node (ref "U$4") (pin "15") (pinfunction "RS232_15") (pintype "bidirectional"))
    )
    (net (code "74") (name "unconnected-(U$4-RTS-Pad14)") (class "Default")
      (node (ref "U$4") (pin "14") (pinfunction "RTS_14") (pintype "bidirectional"))
    )
  )
)
